# SY8003ADFC_2.net
KiCad netlist of a schematic drawn in Altium Designer
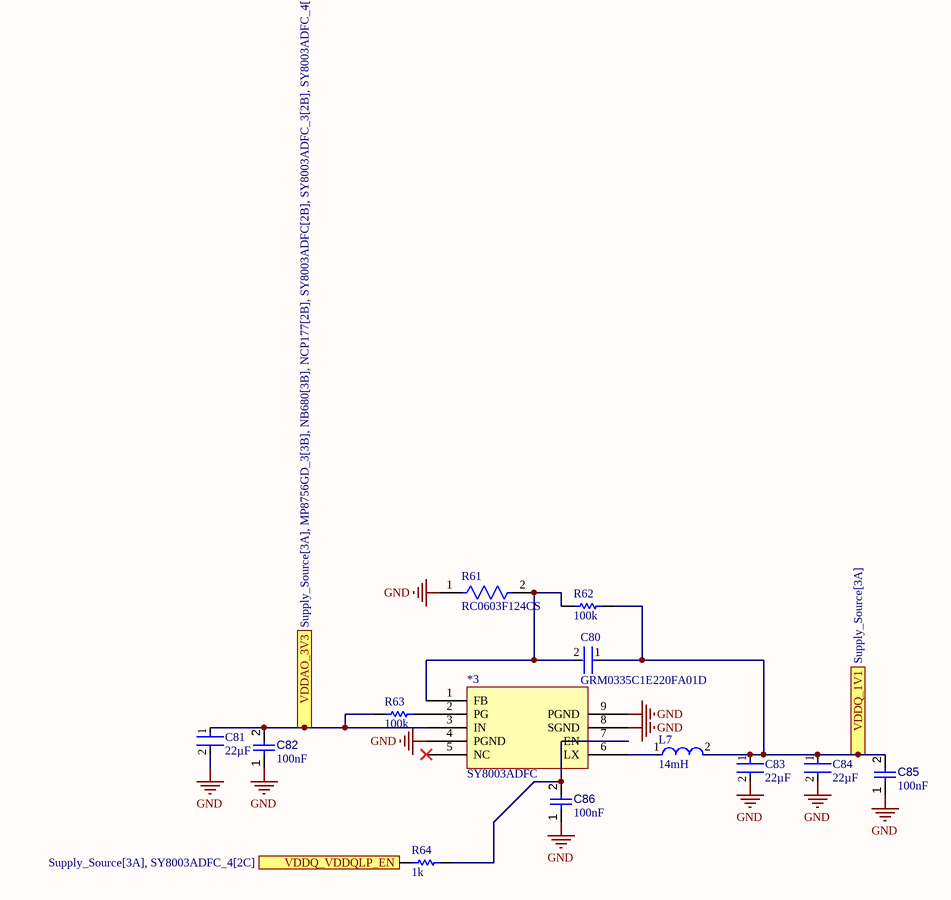
[diagram p0: SY8003ADFC_2.SchDoc]

(export (version "E")
  (design (tool "Eeschema 10.0.6"))
  (components
    (comp (ref "*3")
      (value "SY8003ADFC")
      (footprint "SON127P750X265-8N")
      (description "Switching Regulator, 3A, 1200kHz Switching Freq-Max, PDSO8")
      (libsource (lib "MIGUEL ANGEL ALVAREZ GUZMAN") (part "SY8003ADFC-Symbol-1"))
    )
    (comp (ref "C80")
      (value "GRM0335C1E220FA01D")
      (footprint "FP-GRM033-0_03-IPC_C")
      (description "Chip Multilayer Ceramic Capacitors for General Purpose, 0201, 22pF, C0G, 30ppm/°C, 1%, 25V")
      (fields (field (name "TOLERANCE") "1%"))
      (libsource (lib "Altium Content Vault") (part "b4654b650e69147ec39a6b967a45e02"))
    )
    (comp (ref "C81")
      (value "22µF")
      (footprint "FP-GRM186-0_2-IPC_A")
      (description "6.3V 22uF X5R ±20% 0603 Multilayer Ceramic Capacitors MLCC - SMD/SMT ROHS")
      (fields (field (name "TOLERANCE") "20%") (field (name "Comment") "GRM186R60J226ME15D"))
      (libsource (lib "MIGUEL ANGEL ALVAREZ GUZMAN") (part "02cd4be3c70576c341d710602a673aa"))
    )
    (comp (ref "C82")
      (value "100nF")
      (footprint "CAPC1005X56X25LL10T15")
      (description "Chip Capacitor, 0.1 uF, +/- 5%, 16 V, 0402 (1005 Metric)")
      (fields (field (name "TOLERANCE") "5%") (field (name "Comment") "Capacitor 0.1 uF +/- 5% 16 V 0402"))
      (libsource (lib "MIGUEL ANGEL ALVAREZ GUZMAN") (part "CAP-NP-2"))
    )
    (comp (ref "C83")
      (value "22µF")
      (footprint "FP-GRM186-0_2-IPC_A")
      (description "6.3V 22uF X5R ±20% 0603 Multilayer Ceramic Capacitors MLCC - SMD/SMT ROHS")
      (fields (field (name "TOLERANCE") "20%") (field (name "Comment") "GRM186R60J226ME15D"))
      (libsource (lib "MIGUEL ANGEL ALVAREZ GUZMAN") (part "02cd4be3c70576c341d710602a673aa"))
    )
    (comp (ref "C84")
      (value "22µF")
      (footprint "FP-GRM186-0_2-IPC_A")
      (description "6.3V 22uF X5R ±20% 0603 Multilayer Ceramic Capacitors MLCC - SMD/SMT ROHS")
      (fields (field (name "TOLERANCE") "20%") (field (name "Comment") "GRM186R60J226ME15D"))
      (libsource (lib "MIGUEL ANGEL ALVAREZ GUZMAN") (part "02cd4be3c70576c341d710602a673aa"))
    )
    (comp (ref "C85")
      (value "100nF")
      (footprint "CAPC1005X56X25LL10T15")
      (description "Chip Capacitor, 0.1 uF, +/- 5%, 16 V, 0402 (1005 Metric)")
      (fields (field (name "TOLERANCE") "5%") (field (name "Comment") "Capacitor 0.1 uF +/- 5% 16 V 0402"))
      (libsource (lib "MIGUEL ANGEL ALVAREZ GUZMAN") (part "CAP-NP-2"))
    )
    (comp (ref "C86")
      (value "100nF")
      (footprint "CAPC1005X56X25LL10T15")
      (description "Chip Capacitor, 0.1 uF, +/- 5%, 16 V, 0402 (1005 Metric)")
      (fields (field (name "TOLERANCE") "5%") (field (name "Comment") "Capacitor 0.1 uF +/- 5% 16 V 0402"))
      (libsource (lib "MIGUEL ANGEL ALVAREZ GUZMAN") (part "CAP-NP-2"))
    )
    (comp (ref "L7")
      (value "14mH")
      (footprint "FP-IHLP-2525CZ-FP_2_413x3-MFG")
      (description "Inductor High Current Shielded Wirewound 1.5uH 20% 100KHz 9A 15mOhm DCR 2525 T/R")
      (fields (field (name "TOLERANCE") "20%") (field (name "Comment") "IHLP2525CZER1R5M01"))
      (libsource (lib "MIGUEL ANGEL ALVAREZ GUZMAN") (part "725321dda6339637d4d059423bc1c3c"))
    )
    (comp (ref "R61")
      (value "RC0603F124CS")
      (footprint "FP-RC0603-MFG")
      (description "Res Thick Film 0201 120kΩ 1% 0.05W ±250ppm/°C Molded SMD T/R")
      (fields (field (name "TOLERANCE") "1%"))
      (libsource (lib "Altium Content Vault") (part "1029c3af85768c4190bb7ad29bc67b5"))
    )
    (comp (ref "R62")
      (value "100k")
      (footprint "RESC0603X26X15NL03T05")
      (description "Res General Purpose Thick Film 0201 100k Ohm 1% 1/20W ±200ppm/°C Molded Paper T/R")
      (fields (field (name "TOLERANCE") "1%") (field (name "Comment") "CRG0201F100K"))
      (libsource (lib "MIGUEL ANGEL ALVAREZ GUZMAN") (part "RES"))
    )
    (comp (ref "R63")
      (value "100k")
      (footprint "RESC0603X26X15NL03T05")
      (description "Res General Purpose Thick Film 0201 100k Ohm 1% 1/20W ±200ppm/°C Molded Paper T/R")
      (fields (field (name "TOLERANCE") "1%") (field (name "Comment") "CRG0201F100K"))
      (libsource (lib "MIGUEL ANGEL ALVAREZ GUZMAN") (part "RES"))
    )
    (comp (ref "R64")
      (value "1k")
      (footprint "RESC0603X26X15NL03T05")
      (description "Res General Purpose Thick Film 0201 1k Ohm 1% 1/20W ±200ppm/°C Molded Paper T/R")
      (fields (field (name "TOLERANCE") "1%") (field (name "Comment") "MCRE000140"))
      (libsource (lib "MIGUEL ANGEL ALVAREZ GUZMAN") (part "RES"))
    )
  )
  (nets
    (net (code "1") (name "/VDDAO_3V3") (class "Default")
      (node (ref "*3") (pin "3") (pinfunction "IN_3") (pintype "passive"))
      (node (ref "C81") (pin "1") (pinfunction "1_1") (pintype "passive"))
      (node (ref "C82") (pin "2") (pinfunction "2_2") (pintype "passive"))
      (node (ref "R63") (pin "1") (pinfunction "1_1") (pintype "passive"))
    )
    (net (code "2") (name "/VDDQ_1V1") (class "Default")
      (node (ref "C80") (pin "1") (pinfunction "1_1") (pintype "passive"))
      (node (ref "C83") (pin "1") (pinfunction "1_1") (pintype "passive"))
      (node (ref "C84") (pin "1") (pinfunction "1_1") (pintype "passive"))
      (node (ref "C85") (pin "2") (pinfunction "2_2") (pintype "passive"))
      (node (ref "L7") (pin "2") (pinfunction "2_2") (pintype "passive"))
      (node (ref "R62") (pin "2") (pinfunction "2_2") (pintype "passive"))
    )
    (net (code "3") (name "/VDDQ_VDDQLP_EN") (class "Default")
      (node (ref "R64") (pin "1") (pinfunction "1_1") (pintype "passive"))
    )
    (net (code "4") (name "GND") (class "Default")
      (node (ref "*3") (pin "4") (pinfunction "PGND_4") (pintype "passive"))
      (node (ref "*3") (pin "8") (pinfunction "SGND_8") (pintype "passive"))
      (node (ref "*3") (pin "9") (pinfunction "PGND_9") (pintype "passive"))
      (node (ref "C81") (pin "2") (pinfunction "2_2") (pintype "passive"))
      (node (ref "C82") (pin "1") (pinfunction "1_1") (pintype "passive"))
      (node (ref "C83") (pin "2") (pinfunction "2_2") (pintype "passive"))
      (node (ref "C84") (pin "2") (pinfunction "2_2") (pintype "passive"))
      (node (ref "C85") (pin "1") (pinfunction "1_1") (pintype "passive"))
      (node (ref "C86") (pin "1") (pinfunction "1_1") (pintype "passive"))
      (node (ref "R61") (pin "1") (pinfunction "1_1") (pintype "passive"))
    )
    (net (code "5") (name "Net-(*3-EN)") (class "Default")
      (node (ref "*3") (pin "7") (pinfunction "EN_7") (pintype "passive"))
      (node (ref "C86") (pin "2") (pinfunction "2_2") (pintype "passive"))
      (node (ref "R64") (pin "2") (pinfunction "2_2") (pintype "passive"))
    )
    (net (code "6") (name "Net-(*3-FB)") (class "Default")
      (node (ref "*3") (pin "1") (pinfunction "FB_1") (pintype "passive"))
      (node (ref "C80") (pin "2") (pinfunction "2_2") (pintype "passive"))
      (node (ref "R61") (pin "2") (pinfunction "2_2") (pintype "passive"))
      (node (ref "R62") (pin "1") (pinfunction "1_1") (pintype "passive"))
    )
    (net (code "7") (name "Net-(*3-LX)") (class "Default")
      (node (ref "*3") (pin "6") (pinfunction "LX_6") (pintype "passive"))
      (node (ref "L7") (pin "1") (pinfunction "1_1") (pintype "passive"))
    )
    (net (code "8") (name "Net-(*3-PG)") (class "Default")
      (node (ref "*3") (pin "2") (pinfunction "PG_2") (pintype "passive"))
      (node (ref "R63") (pin "2") (pinfunction "2_2") (pintype "passive"))
    )
    (net (code "9") (name "unconnected-(*3-NC-Pad5)") (class "Default")
      (node (ref "*3") (pin "5") (pinfunction "NC_5") (pintype "passive+no_connect"))
    )
  )
)
